# M1_Schematic_2.net
KiCad netlist of a schematic drawn in Altium Designer
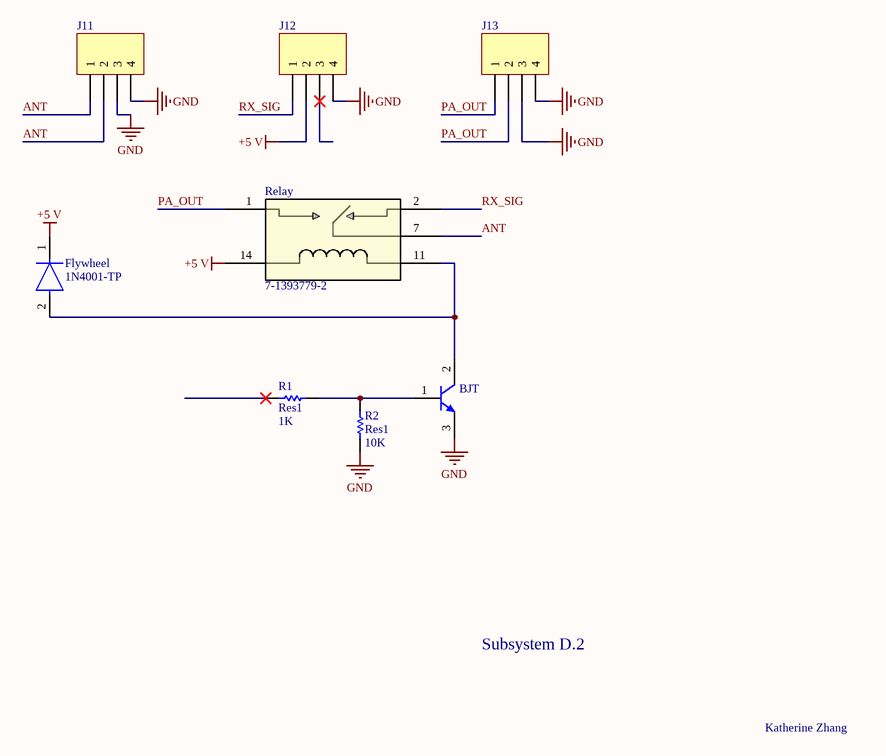
[diagram p0: M1 Schematic 2.SchDoc]

(export (version "E")
  (design (tool "Eeschema 10.0.6"))
  (components
    (comp (ref "BJT")
      (value "2N2222A")
      (footprint "STM-TO-18-3")
      (description "High Speed Switch, 0.6 A IC, -65 to 175 degC, 3-Pin TO-18, RoHS, Bulk")
      (fields (field (name "MANUFACTURER") "STMicroelectronics"))
      (libsource (lib "Altium Content Vault") (part "NPN_B1C2E3-3"))
    )
    (comp (ref "Flywheel")
      (value "1N4001-TP")
      (footprint "FP-DO-41-MFG")
      (description "DIODE GEN PURP 50V 1A DO41")
      (fields
        (field (name "MANUFACTURER") "Micro Commercial")
        (field (name "OCTOPART") "https://octopart.com/1n4001-tp-mcc-730241")
      )
      (libsource (lib "Altium Content Vault") (part "d7152d700b627762746794eb795d46e"))
    )
    (comp (ref "J11")
      (value "Header 4")
      (footprint "HDR1X4")
      (description "Conn Header Vert 4POS 2.54MM")
      (fields
        (field (name "MANUFACTURER") "Sullins")
        (field (name "MANUFACTURER PART NUMBER") "PRPC004SAAN-RC")
        (field (name "PUBLISHER") "Altium Limited")
      )
      (libsource (lib "Miscellaneous Connectors") (part "Header 4"))
    )
    (comp (ref "J12")
      (value "Header 4")
      (footprint "HDR1X4")
      (description "Conn Header Vert 4POS 2.54MM")
      (fields
        (field (name "MANUFACTURER") "Sullins")
        (field (name "MANUFACTURER PART NUMBER") "PRPC004SAAN-RC")
        (field (name "PUBLISHER") "Altium Limited")
      )
      (libsource (lib "Miscellaneous Connectors") (part "Header 4"))
    )
    (comp (ref "J13")
      (value "Header 4")
      (footprint "HDR1X4")
      (description "Conn Header Vert 4POS 2.54MM")
      (fields
        (field (name "MANUFACTURER") "Sullins")
        (field (name "MANUFACTURER PART NUMBER") "PRPC004SAAN-RC")
        (field (name "PUBLISHER") "Altium Limited")
      )
      (libsource (lib "Miscellaneous Connectors") (part "Header 4"))
    )
    (comp (ref "R1")
      (value "Res1")
      (footprint "AXIAL-0.1-RES")
      (description "Resistor")
      (fields
        (field (name "MANUFACTURER PART NUMBER") "CFR-25JB-52-1K")
        (field (name "TOLERANCE") "0.05")
        (field (name "ALTIUM_VALUE") "1K")
        (field (name "PUBLISHER") "Altium Limited")
      )
      (libsource (lib "ECE295-Resistors-TH") (part "RES 1K OHM 5% 1/4W AXIAL"))
    )
    (comp (ref "R2")
      (value "Res1")
      (footprint "AXIAL-0.1-RES")
      (description "Resistor")
      (fields
        (field (name "ALTIUM_VALUE") "10K")
        (field (name "MANUFACTURER PART NUMBER") "CFR-25JB-52-10K")
        (field (name "TOLERANCE") "0.05")
        (field (name "PUBLISHER") "Altium Limited")
      )
      (libsource (lib "ECE295-Resistors-TH") (part "RES 10K OHM 5% 1/4W AXIAL"))
    )
    (comp (ref "Relay")
      (value "7-1393779-2")
      (footprint "RELAY_7-1393779-2")
      (description "No Description Available")
      (fields (field (name "COPYRIGHT") "Copyright (C) 2022 Ultra Librarian. All rights reserved."))
      (libsource (lib "7-1393779-2") (part "7-1393779-2"))
    )
  )
  (nets
    (net (code "1") (name "+5 V") (class "Default")
      (node (ref "Flywheel") (pin "1") (pinfunction "C_1") (pintype "passive"))
      (node (ref "J12") (pin "2") (pinfunction "2_2") (pintype "passive"))
      (node (ref "Relay") (pin "14") (pinfunction "12_14") (pintype "passive"))
    )
    (net (code "2") (name "/ANT") (class "Default")
      (node (ref "J11") (pin "1") (pinfunction "1_1") (pintype "passive"))
      (node (ref "J11") (pin "2") (pinfunction "2_2") (pintype "passive"))
      (node (ref "Relay") (pin "7") (pinfunction "7_7") (pintype "passive"))
    )
    (net (code "3") (name "/PA_OUT") (class "Default")
      (node (ref "J13") (pin "1") (pinfunction "1_1") (pintype "passive"))
      (node (ref "J13") (pin "2") (pinfunction "2_2") (pintype "passive"))
      (node (ref "Relay") (pin "1") (pinfunction "1_1") (pintype "passive"))
    )
    (net (code "4") (name "/RX_SIG") (class "Default")
      (node (ref "J12") (pin "1") (pinfunction "1_1") (pintype "passive"))
      (node (ref "Relay") (pin "2") (pinfunction "2_2") (pintype "passive"))
    )
    (net (code "5") (name "GND") (class "Default")
      (node (ref "BJT") (pin "3") (pinfunction "E_3") (pintype "passive"))
      (node (ref "J11") (pin "3") (pinfunction "3_3") (pintype "passive"))
      (node (ref "J11") (pin "4") (pinfunction "4_4") (pintype "passive"))
      (node (ref "J12") (pin "4") (pinfunction "4_4") (pintype "passive"))
      (node (ref "J13") (pin "3") (pinfunction "3_3") (pintype "passive"))
      (node (ref "J13") (pin "4") (pinfunction "4_4") (pintype "passive"))
      (node (ref "R2") (pin "1") (pinfunction "1_1") (pintype "passive"))
    )
    (net (code "6") (name "Net-(BJT-B)") (class "Default")
      (node (ref "BJT") (pin "1") (pinfunction "B_1") (pintype "passive"))
      (node (ref "R1") (pin "2") (pinfunction "2_2") (pintype "passive"))
      (node (ref "R2") (pin "2") (pinfunction "2_2") (pintype "passive"))
    )
    (net (code "7") (name "Net-(BJT-C)") (class "Default")
      (node (ref "BJT") (pin "2") (pinfunction "C_2") (pintype "passive"))
      (node (ref "Flywheel") (pin "2") (pinfunction "A_2") (pintype "passive"))
      (node (ref "Relay") (pin "11") (pinfunction "11_11") (pintype "passive"))
    )
    (net (code "8") (name "unconnected-(J12-Pad3)") (class "Default")
      (node (ref "J12") (pin "3") (pinfunction "3_3") (pintype "passive+no_connect"))
    )
    (net (code "9") (name "unconnected-(R1-Pad1)") (class "Default")
      (node (ref "R1") (pin "1") (pinfunction "1_1") (pintype "passive+no_connect"))
    )
  )
)
